# CH32V203_Wireless_Charge_V2_0.net
KiCad netlist of a schematic drawn in EasyEDA Pro
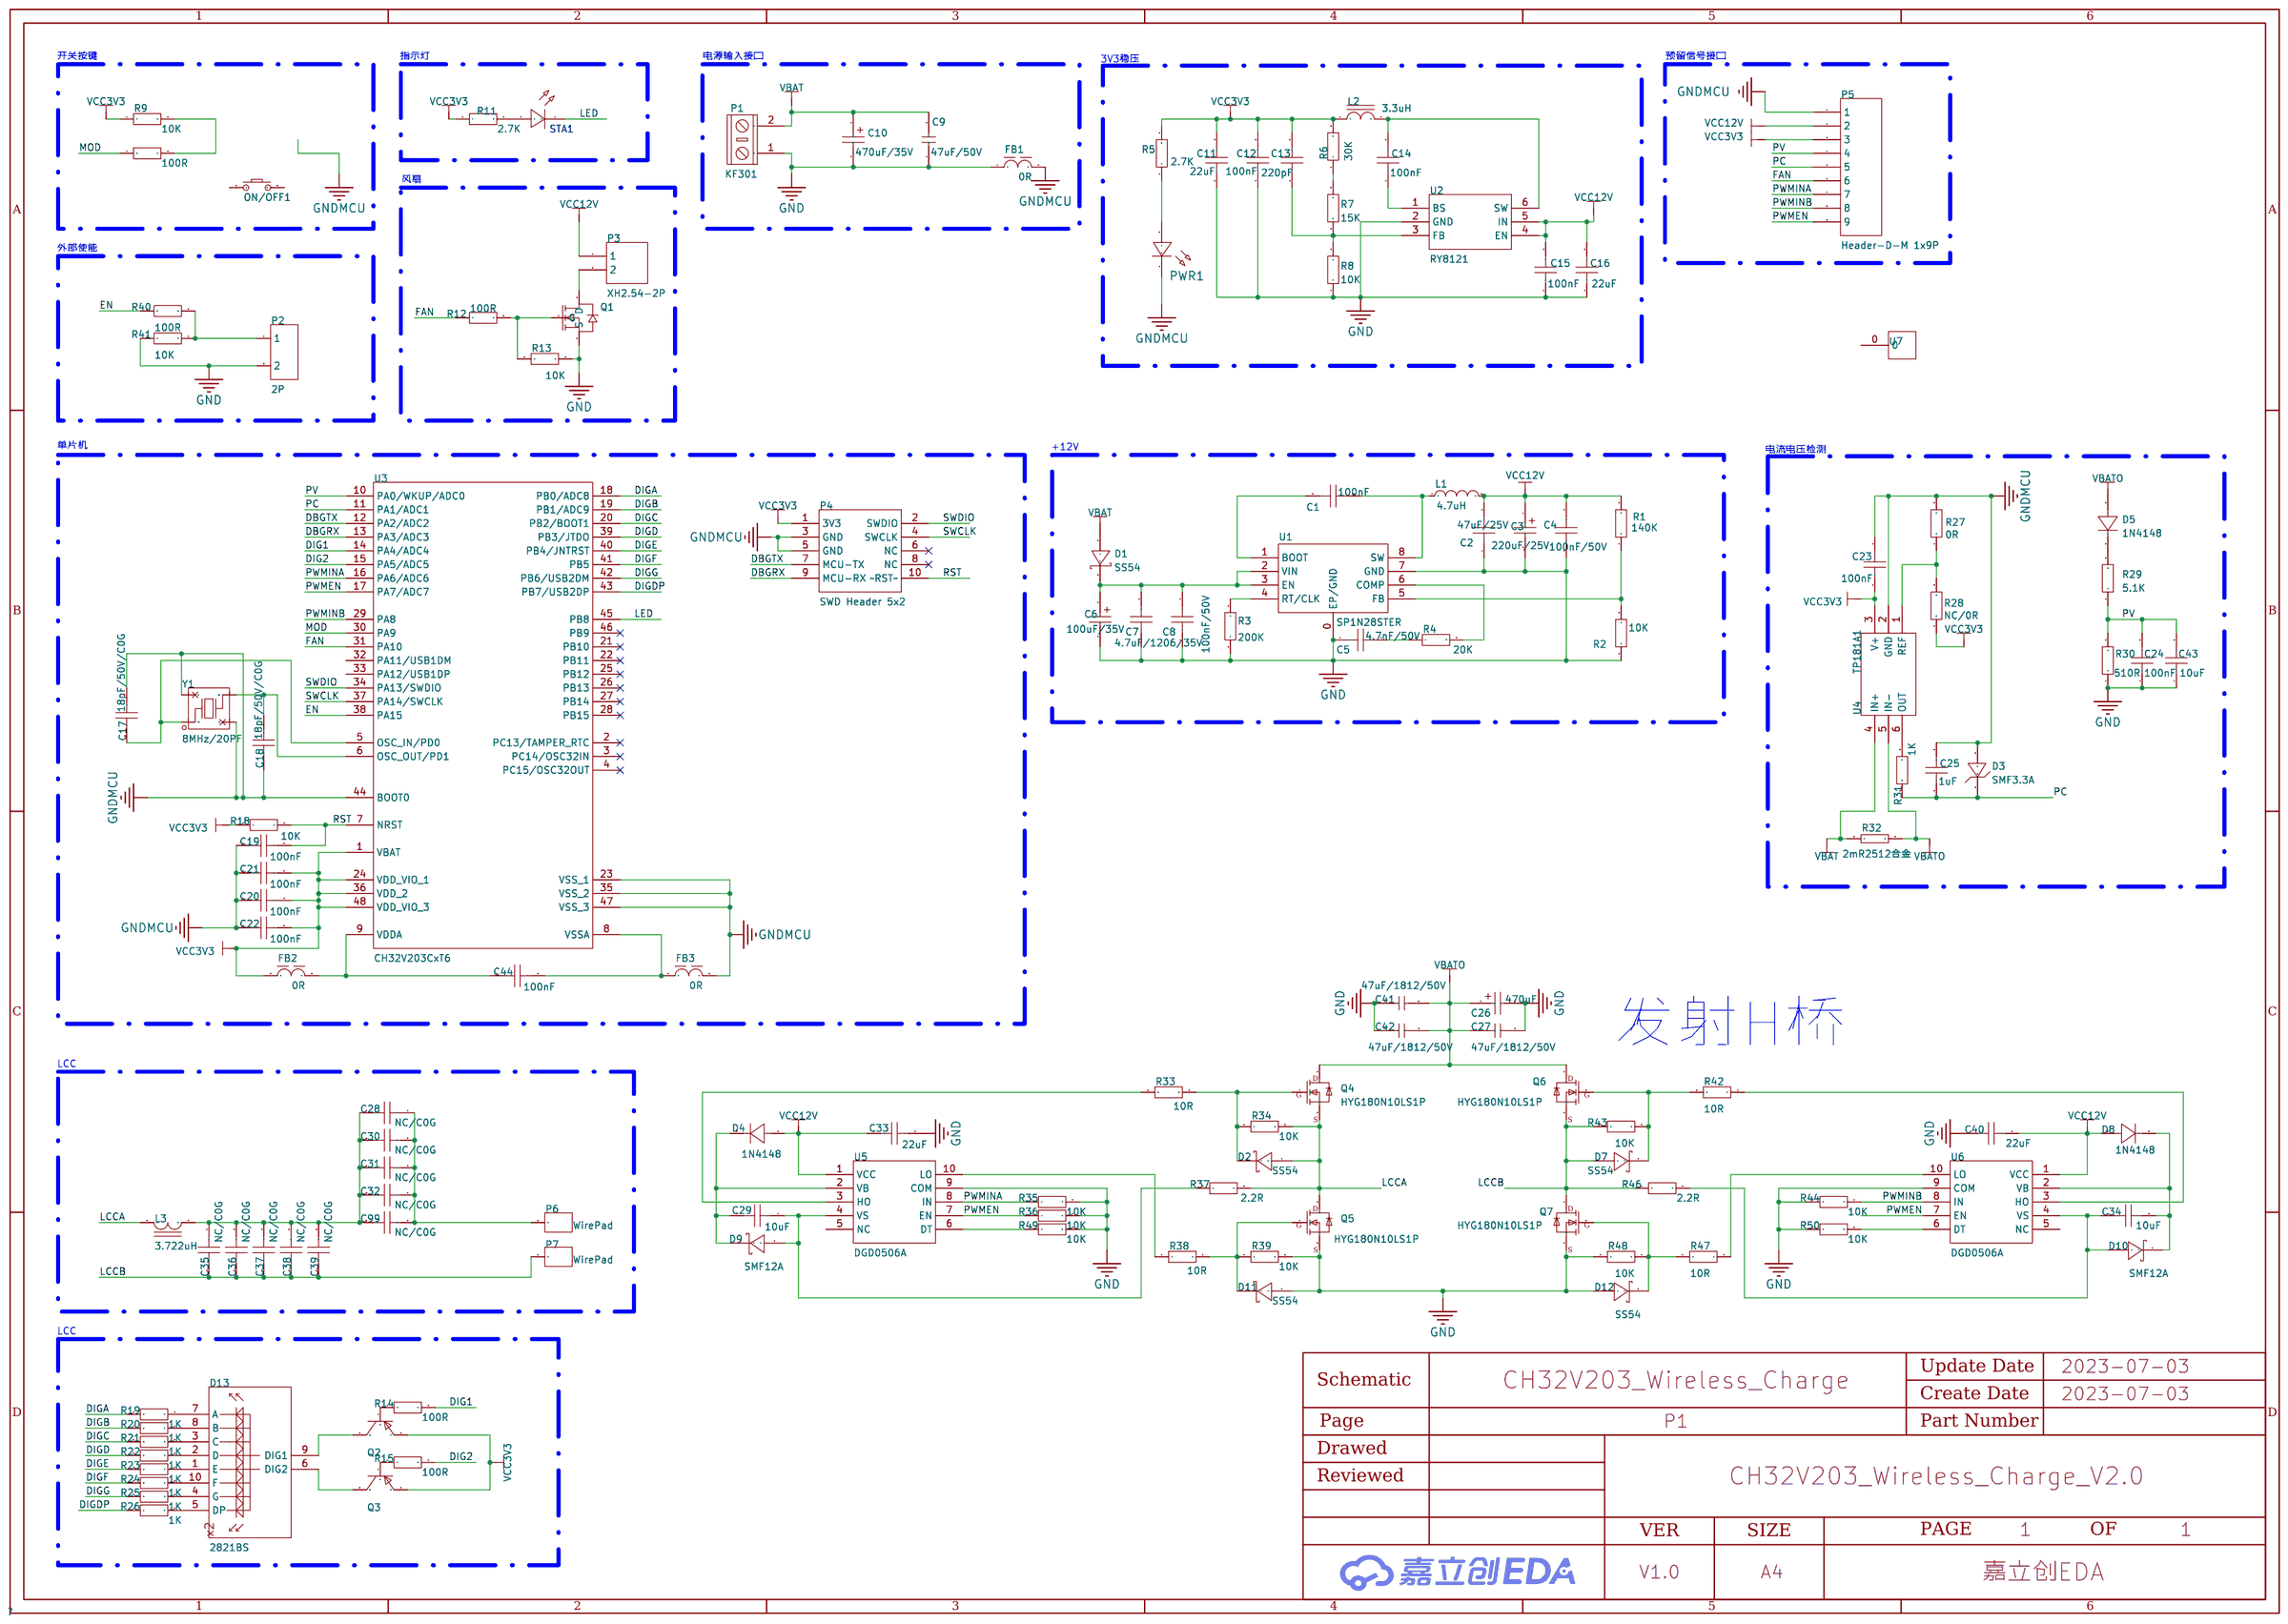
[diagram p0: schematic sheet]

(export (version "E")
  (design (tool "Eeschema 10.0.6"))
  (components
    (comp (ref "C1")
      (value "100nF")
      (footprint "easyedapro:C0603")
      (libsource (lib "easyedapro") (part "CapAcitance"))
    )
    (comp (ref "C2")
      (value "47uF/25V")
      (footprint "easyedapro:C0603")
      (libsource (lib "easyedapro") (part "CapAcitance"))
    )
    (comp (ref "C3")
      (value "220uF/25V")
      (footprint "easyedapro:Cap-S-D 2.5-6.3X8")
      (libsource (lib "easyedapro") (part "S-D 220uF 25V 6.3x8"))
    )
    (comp (ref "C4")
      (value "100nF/50V")
      (footprint "easyedapro:C0603")
      (libsource (lib "easyedapro") (part "CapAcitance"))
    )
    (comp (ref "C5")
      (value "4.7nF/50V")
      (footprint "easyedapro:C0603")
      (libsource (lib "easyedapro") (part "CapAcitance"))
    )
    (comp (ref "C6")
      (value "100uF/35V")
      (footprint "easyedapro:Cap-S-D 2.5-6.3X8")
      (libsource (lib "easyedapro") (part "S-D 100uF 35V 6.3x8"))
    )
    (comp (ref "C7")
      (value "4.7uF/1206/35V")
      (footprint "easyedapro:C0603")
      (libsource (lib "easyedapro") (part "CapAcitance"))
    )
    (comp (ref "C8")
      (value "100nF/50V")
      (footprint "easyedapro:C0603")
      (libsource (lib "easyedapro") (part "CapAcitance"))
    )
    (comp (ref "C9")
      (value "47uF/50V")
      (footprint "easyedapro:CAPC4532[1812]S")
      (libsource (lib "easyedapro") (part "47uF 1812 50V X5R"))
    )
    (comp (ref "C10")
      (value "470uF/35V")
      (footprint "easyedapro:Cap-S-D 3.5-8x14")
      (libsource (lib "easyedapro") (part "S-D 470uF 35V 8x14"))
    )
    (comp (ref "C11")
      (value "22uF")
      (footprint "easyedapro:C0603")
      (libsource (lib "easyedapro") (part "CapAcitance"))
    )
    (comp (ref "C12")
      (value "100nF")
      (footprint "easyedapro:C0603")
      (libsource (lib "easyedapro") (part "CapAcitance"))
    )
    (comp (ref "C13")
      (value "220pF")
      (footprint "easyedapro:C0603")
      (libsource (lib "easyedapro") (part "CapAcitance"))
    )
    (comp (ref "C14")
      (value "100nF")
      (footprint "easyedapro:C0603")
      (libsource (lib "easyedapro") (part "CapAcitance"))
    )
    (comp (ref "C15")
      (value "100nF")
      (footprint "easyedapro:C0603")
      (libsource (lib "easyedapro") (part "CapAcitance"))
    )
    (comp (ref "C16")
      (value "22uF")
      (footprint "easyedapro:C0603")
      (libsource (lib "easyedapro") (part "CapAcitance"))
    )
    (comp (ref "C17")
      (value "18pF/50V/C0G")
      (footprint "easyedapro:C0603")
      (libsource (lib "easyedapro") (part "CapAcitance"))
    )
    (comp (ref "C18")
      (value "18pF/50V/C0G")
      (footprint "easyedapro:C0603")
      (libsource (lib "easyedapro") (part "CapAcitance"))
    )
    (comp (ref "C19")
      (value "100nF")
      (footprint "easyedapro:C0603")
      (libsource (lib "easyedapro") (part "CapAcitance"))
    )
    (comp (ref "C20")
      (value "100nF")
      (footprint "easyedapro:C0603")
      (libsource (lib "easyedapro") (part "CapAcitance"))
    )
    (comp (ref "C21")
      (value "100nF")
      (footprint "easyedapro:C0603")
      (libsource (lib "easyedapro") (part "CapAcitance"))
    )
    (comp (ref "C22")
      (value "100nF")
      (footprint "easyedapro:C0603")
      (libsource (lib "easyedapro") (part "CapAcitance"))
    )
    (comp (ref "C23")
      (value "100nF")
      (footprint "easyedapro:C0603")
      (libsource (lib "easyedapro") (part "CapAcitance"))
    )
    (comp (ref "C24")
      (value "100nF")
      (footprint "easyedapro:C0603")
      (libsource (lib "easyedapro") (part "CapAcitance"))
    )
    (comp (ref "C25")
      (value "1uF")
      (footprint "easyedapro:C0603")
      (libsource (lib "easyedapro") (part "CapAcitance"))
    )
    (comp (ref "C26")
      (value "470uF")
      (footprint "easyedapro:Cap-S-D 3.5-8x14")
      (libsource (lib "easyedapro") (part "S-D 470uF 35V 8x14"))
    )
    (comp (ref "C27")
      (value "47uF/1812/50V")
      (footprint "easyedapro:CAPC4532[1812]S")
      (libsource (lib "easyedapro") (part "47uF 1812 50V X5R"))
    )
    (comp (ref "C28")
      (value "NC/C0G")
      (footprint "easyedapro:C0603")
      (libsource (lib "easyedapro") (part "CapAcitance"))
    )
    (comp (ref "C29")
      (value "10uF")
      (footprint "easyedapro:C0603")
      (libsource (lib "easyedapro") (part "CapAcitance"))
    )
    (comp (ref "C30")
      (value "NC/C0G")
      (footprint "easyedapro:C0603")
      (libsource (lib "easyedapro") (part "CapAcitance"))
    )
    (comp (ref "C31")
      (value "NC/C0G")
      (footprint "easyedapro:C0603")
      (libsource (lib "easyedapro") (part "CapAcitance"))
    )
    (comp (ref "C32")
      (value "NC/C0G")
      (footprint "easyedapro:C0603")
      (libsource (lib "easyedapro") (part "CapAcitance"))
    )
    (comp (ref "C33")
      (value "22uF")
      (footprint "easyedapro:C0603")
      (libsource (lib "easyedapro") (part "CapAcitance"))
    )
    (comp (ref "C34")
      (value "10uF")
      (footprint "easyedapro:C0603")
      (libsource (lib "easyedapro") (part "CapAcitance"))
    )
    (comp (ref "C35")
      (value "NC/C0G")
      (footprint "easyedapro:C0603")
      (libsource (lib "easyedapro") (part "CapAcitance"))
    )
    (comp (ref "C36")
      (value "NC/C0G")
      (footprint "easyedapro:C0603")
      (libsource (lib "easyedapro") (part "CapAcitance"))
    )
    (comp (ref "C37")
      (value "NC/C0G")
      (footprint "easyedapro:C0603")
      (libsource (lib "easyedapro") (part "CapAcitance"))
    )
    (comp (ref "C38")
      (value "NC/C0G")
      (footprint "easyedapro:C0603")
      (libsource (lib "easyedapro") (part "CapAcitance"))
    )
    (comp (ref "C39")
      (value "NC/C0G")
      (footprint "easyedapro:C0603")
      (libsource (lib "easyedapro") (part "CapAcitance"))
    )
    (comp (ref "C40")
      (value "22uF")
      (footprint "easyedapro:C0603")
      (libsource (lib "easyedapro") (part "CapAcitance"))
    )
    (comp (ref "C41")
      (value "47uF/1812/50V")
      (footprint "easyedapro:CAPC4532[1812]S")
      (libsource (lib "easyedapro") (part "47uF 1812 50V X5R"))
    )
    (comp (ref "C42")
      (value "47uF/1812/50V")
      (footprint "easyedapro:CAPC4532[1812]S")
      (libsource (lib "easyedapro") (part "47uF 1812 50V X5R"))
    )
    (comp (ref "C43")
      (value "10uF")
      (footprint "easyedapro:C0603")
      (libsource (lib "easyedapro") (part "CapAcitance"))
    )
    (comp (ref "C44")
      (value "100nF")
      (footprint "easyedapro:C0603")
      (libsource (lib "easyedapro") (part "CapAcitance"))
    )
    (comp (ref "C99")
      (value "NC/C0G")
      (footprint "easyedapro:C0603")
      (libsource (lib "easyedapro") (part "CapAcitance"))
    )
    (comp (ref "D1")
      (value "SS54")
      (footprint "easyedapro:SMA_L4.4-W2.8-LS5.4-R-RD")
      (description "直流反向耐压(Vr):40V;平均整流电流(Io):5A;正向压降(Vf):550mV@5A;")
      (fields (field (name "Manufacturer") "MDD"))
      (libsource (lib "easyedapro") (part "SS54_C22452"))
    )
    (comp (ref "D2")
      (value "SS54")
      (footprint "easyedapro:SMA_L4.4-W2.8-LS5.4-R-RD")
      (description "直流反向耐压(Vr):40V;平均整流电流(Io):5A;正向压降(Vf):550mV@5A;")
      (fields (field (name "Manufacturer") "MDD"))
      (libsource (lib "easyedapro") (part "SS54_C22452"))
    )
    (comp (ref "D3")
      (value "SMF3.3A")
      (footprint "easyedapro:SOD-123_L2.8-W1.8-LS3.7-RD")
      (description "极性:单向;反向截止电压(Vrwm):3.3V;击穿电压:5.2V;反向漏电流(Ir):600uA;峰值脉冲电流(Ipp)@10/1000μs:25A;最大钳位电压:8V;")
      (fields (field (name "Manufacturer") "DOWO(东沃)"))
      (libsource (lib "easyedapro") (part "SMF3.3A"))
    )
    (comp (ref "D4")
      (value "1N4148")
      (footprint "easyedapro:SOD-123_L2.7-W1.6-LS3.7-RD")
      (fields (field (name "Manufacturer") "FUXINSEMI(富芯森美)"))
      (libsource (lib "easyedapro") (part "1N4148W_C908248"))
    )
    (comp (ref "D5")
      (value "1N4148")
      (footprint "easyedapro:SOD-123_L2.7-W1.6-LS3.7-RD")
      (fields (field (name "Manufacturer") "FUXINSEMI(富芯森美)"))
      (libsource (lib "easyedapro") (part "1N4148W_C908248"))
    )
    (comp (ref "D7")
      (value "SS54")
      (footprint "easyedapro:SMA_L4.4-W2.8-LS5.4-R-RD")
      (description "直流反向耐压(Vr):40V;平均整流电流(Io):5A;正向压降(Vf):550mV@5A;")
      (fields (field (name "Manufacturer") "MDD"))
      (libsource (lib "easyedapro") (part "SS54_C22452"))
    )
    (comp (ref "D8")
      (value "1N4148")
      (footprint "easyedapro:SOD-123_L2.7-W1.6-LS3.7-RD")
      (fields (field (name "Manufacturer") "FUXINSEMI(富芯森美)"))
      (libsource (lib "easyedapro") (part "1N4148W_C908248"))
    )
    (comp (ref "D9")
      (value "SMF12A")
      (footprint "easyedapro:SOD-123F_L2.8-W1.8-LS3.7-RD")
      (description "极性:单向;反向截止电压(Vrwm):12V;击穿电压:13.3V;峰值脉冲电流(Ipp)@10/1000μs:-;最大钳位电压:19.9V;峰值脉冲功率(Ppp)@10/1000μs:200W;")
      (fields (field (name "Manufacturer") "Littelfuse(美国力特)"))
      (libsource (lib "easyedapro") (part "SMF12A_C207255"))
    )
    (comp (ref "D10")
      (value "SMF12A")
      (footprint "easyedapro:SOD-123F_L2.8-W1.8-LS3.7-RD")
      (description "极性:单向;反向截止电压(Vrwm):12V;击穿电压:13.3V;峰值脉冲电流(Ipp)@10/1000μs:-;最大钳位电压:19.9V;峰值脉冲功率(Ppp)@10/1000μs:200W;")
      (fields (field (name "Manufacturer") "Littelfuse(美国力特)"))
      (libsource (lib "easyedapro") (part "SMF12A_C207255"))
    )
    (comp (ref "D11")
      (value "SS54")
      (footprint "easyedapro:SMA_L4.4-W2.8-LS5.4-R-RD")
      (description "直流反向耐压(Vr):40V;平均整流电流(Io):5A;正向压降(Vf):550mV@5A;")
      (fields (field (name "Manufacturer") "MDD"))
      (libsource (lib "easyedapro") (part "SS54_C22452"))
    )
    (comp (ref "D12")
      (value "SS54")
      (footprint "easyedapro:SMA_L4.4-W2.8-LS5.4-R-RD")
      (description "直流反向耐压(Vr):40V;平均整流电流(Io):5A;正向压降(Vf):550mV@5A;")
      (fields (field (name "Manufacturer") "MDD"))
      (libsource (lib "easyedapro") (part "SS54_C22452"))
    )
    (comp (ref "D13")
      (value "2821BS")
      (footprint "easyedapro:2821AS/BS")
      (libsource (lib "easyedapro") (part "2821BS"))
    )
    (comp (ref "FB1")
      (value "0R")
      (footprint "easyedapro:INDC1608[0603]S")
      (libsource (lib "easyedapro") (part "FB-Chip"))
    )
    (comp (ref "FB2")
      (value "0R")
      (footprint "easyedapro:INDC1608[0603]S")
      (libsource (lib "easyedapro") (part "FB-Chip"))
    )
    (comp (ref "FB3")
      (value "0R")
      (footprint "easyedapro:INDC1608[0603]S")
      (libsource (lib "easyedapro") (part "FB-Chip"))
    )
    (comp (ref "L1")
      (value "4.7uH")
      (footprint "easyedapro:IND-SMD_L7.3-W6.6")
      (description "电感值:4.7uH;精度:±20%;额定电流:5.5A;饱和电流(Isat):7A;直流电阻(DCR):37mΩ;")
      (fields (field (name "Manufacturer Part") "MCS0630-4R7MPY1") (field (name "Manufacturer") "PSA(信昌电陶)"))
      (libsource (lib "easyedapro") (part "MCS0630-4R7MPY1"))
    )
    (comp (ref "L2")
      (value "3.3uH")
      (footprint "easyedapro:0402 TPC 4*4*2")
      (libsource (lib "easyedapro") (part "Ind-Power_1"))
    )
    (comp (ref "L3")
      (value "3.722uH")
      (footprint "easyedapro:T94/106-LAY")
      (libsource (lib "easyedapro") (part "Ind-Power_2"))
    )
    (comp (ref "ON/OFF1")
      (value "Button")
      (footprint "easyedapro:KEY-2-DIP-6*6-S")
      (libsource (lib "easyedapro") (part "KEY"))
    )
    (comp (ref "P1")
      (value "KF301")
      (footprint "easyedapro:KF/WJ/DG 301-2p-5.0mm")
      (libsource (lib "easyedapro") (part "KF/WJ/DG 30x"))
    )
    (comp (ref "P2")
      (value "2P")
      (footprint "easyedapro:HDR-TH_2P-P2.54-V-M-1")
      (fields (field (name "Manufacturer") "TEConnectivity(美国泰科)"))
      (libsource (lib "easyedapro") (part "Header-Male-2.54_1x2"))
    )
    (comp (ref "P3")
      (value "XH2.54-2P")
      (footprint "easyedapro:XH2.54-2P-DV")
      (libsource (lib "easyedapro") (part "XH2.54-2P"))
    )
    (comp (ref "P4")
      (value "SWD Header 5x2")
      (footprint "easyedapro:HDR2X5-M")
      (libsource (lib "easyedapro") (part "SWD Header 5x2"))
    )
    (comp (ref "P5")
      (value "Header-D-M1x9P")
      (footprint "easyedapro:HDR1X9-M")
      (libsource (lib "easyedapro") (part "Header-D-M 1x9P"))
    )
    (comp (ref "P6")
      (value "WirePad")
      (footprint "easyedapro:WirePad-4x6")
      (libsource (lib "easyedapro") (part "WirePad"))
    )
    (comp (ref "P7")
      (value "WirePad")
      (footprint "easyedapro:WirePad-4x6")
      (libsource (lib "easyedapro") (part "WirePad"))
    )
    (comp (ref "PWR1")
      (value "~")
      (footprint "easyedapro:LED_0603")
      (libsource (lib "easyedapro") (part "LED_R"))
    )
    (comp (ref "Q1")
      (value "~")
      (footprint "easyedapro:SOT-23-3_L2.9-W1.3-P1.90-LS2.4-BR")
      (libsource (lib "easyedapro") (part "N_MOS"))
    )
    (comp (ref "Q2")
      (value "~")
      (footprint "easyedapro:S8550P_SOT")
      (libsource (lib "easyedapro") (part "PNP"))
    )
    (comp (ref "Q3")
      (value "~")
      (footprint "easyedapro:S8550P_SOT")
      (libsource (lib "easyedapro") (part "PNP"))
    )
    (comp (ref "Q4")
      (value "HYG180N10LS1P")
      (footprint "easyedapro:TO-220-LAY")
      (libsource (lib "easyedapro") (part "HYG180N10LS1P"))
    )
    (comp (ref "Q5")
      (value "HYG180N10LS1P")
      (footprint "easyedapro:TO-220-LAY")
      (libsource (lib "easyedapro") (part "HYG180N10LS1P"))
    )
    (comp (ref "Q6")
      (value "HYG180N10LS1P")
      (footprint "easyedapro:TO-220-LAY")
      (libsource (lib "easyedapro") (part "HYG180N10LS1P"))
    )
    (comp (ref "Q7")
      (value "HYG180N10LS1P")
      (footprint "easyedapro:TO-220-LAY")
      (libsource (lib "easyedapro") (part "HYG180N10LS1P"))
    )
    (comp (ref "R1") (value "140K") (footprint "easyedapro:R0603") (libsource (lib "easyedapro") (part "电阻")))
    (comp (ref "R2") (value "10K") (footprint "easyedapro:R0603") (libsource (lib "easyedapro") (part "电阻")))
    (comp (ref "R3") (value "200K") (footprint "easyedapro:R0603") (libsource (lib "easyedapro") (part "电阻")))
    (comp (ref "R4") (value "20K") (footprint "easyedapro:R0603") (libsource (lib "easyedapro") (part "电阻")))
    (comp (ref "R5") (value "2.7K") (footprint "easyedapro:R0603") (libsource (lib "easyedapro") (part "电阻")))
    (comp (ref "R6") (value "30K") (footprint "easyedapro:R0603") (libsource (lib "easyedapro") (part "电阻")))
    (comp (ref "R7") (value "15K") (footprint "easyedapro:R0603") (libsource (lib "easyedapro") (part "电阻")))
    (comp (ref "R8") (value "10K") (footprint "easyedapro:R0603") (libsource (lib "easyedapro") (part "电阻")))
    (comp (ref "R9") (value "10K") (footprint "easyedapro:R0603") (libsource (lib "easyedapro") (part "电阻")))
    (comp (ref "R10")
      (value "100R")
      (footprint "easyedapro:R0603")
      (libsource (lib "easyedapro") (part "电阻"))
    )
    (comp (ref "R11")
      (value "2.7K")
      (footprint "easyedapro:R0603")
      (libsource (lib "easyedapro") (part "电阻"))
    )
    (comp (ref "R12")
      (value "100R")
      (footprint "easyedapro:R0603")
      (libsource (lib "easyedapro") (part "电阻"))
    )
    (comp (ref "R13") (value "10K") (footprint "easyedapro:R0603") (libsource (lib "easyedapro") (part "电阻")))
    (comp (ref "R14")
      (value "100R")
      (footprint "easyedapro:R0603")
      (libsource (lib "easyedapro") (part "电阻"))
    )
    (comp (ref "R15")
      (value "100R")
      (footprint "easyedapro:R0603")
      (libsource (lib "easyedapro") (part "电阻"))
    )
    (comp (ref "R18") (value "10K") (footprint "easyedapro:R0603") (libsource (lib "easyedapro") (part "电阻")))
    (comp (ref "R19") (value "1K") (footprint "easyedapro:R0603") (libsource (lib "easyedapro") (part "电阻")))
    (comp (ref "R20") (value "1K") (footprint "easyedapro:R0603") (libsource (lib "easyedapro") (part "电阻")))
    (comp (ref "R21") (value "1K") (footprint "easyedapro:R0603") (libsource (lib "easyedapro") (part "电阻")))
    (comp (ref "R22") (value "1K") (footprint "easyedapro:R0603") (libsource (lib "easyedapro") (part "电阻")))
    (comp (ref "R23") (value "1K") (footprint "easyedapro:R0603") (libsource (lib "easyedapro") (part "电阻")))
    (comp (ref "R24") (value "1K") (footprint "easyedapro:R0603") (libsource (lib "easyedapro") (part "电阻")))
    (comp (ref "R25") (value "1K") (footprint "easyedapro:R0603") (libsource (lib "easyedapro") (part "电阻")))
    (comp (ref "R26") (value "1K") (footprint "easyedapro:R0603") (libsource (lib "easyedapro") (part "电阻")))
    (comp (ref "R27") (value "0R") (footprint "easyedapro:R0603") (libsource (lib "easyedapro") (part "电阻")))
    (comp (ref "R28")
      (value "NC/0R")
      (footprint "easyedapro:R0603")
      (libsource (lib "easyedapro") (part "电阻"))
    )
    (comp (ref "R29")
      (value "5.1K")
      (footprint "easyedapro:R0603")
      (libsource (lib "easyedapro") (part "电阻"))
    )
    (comp (ref "R30")
      (value "510R")
      (footprint "easyedapro:R0603")
      (libsource (lib "easyedapro") (part "电阻"))
    )
    (comp (ref "R31") (value "1K") (footprint "easyedapro:R0603") (libsource (lib "easyedapro") (part "电阻")))
    (comp (ref "R32")
      (value "2mR2512合金")
      (footprint "easyedapro:RESC6332[2512]S")
      (libsource (lib "easyedapro") (part "Res-Chip_10"))
    )
    (comp (ref "R33") (value "10R") (footprint "easyedapro:R0603") (libsource (lib "easyedapro") (part "电阻")))
    (comp (ref "R34") (value "10K") (footprint "easyedapro:R0603") (libsource (lib "easyedapro") (part "电阻")))
    (comp (ref "R35") (value "10K") (footprint "easyedapro:R0603") (libsource (lib "easyedapro") (part "电阻")))
    (comp (ref "R36") (value "10K") (footprint "easyedapro:R0603") (libsource (lib "easyedapro") (part "电阻")))
    (comp (ref "R37")
      (value "2.2R")
      (footprint "easyedapro:R0603")
      (libsource (lib "easyedapro") (part "电阻"))
    )
    (comp (ref "R38") (value "10R") (footprint "easyedapro:R0603") (libsource (lib "easyedapro") (part "电阻")))
    (comp (ref "R39") (value "10K") (footprint "easyedapro:R0603") (libsource (lib "easyedapro") (part "电阻")))
    (comp (ref "R40")
      (value "100R")
      (footprint "easyedapro:R0603")
      (libsource (lib "easyedapro") (part "电阻"))
    )
    (comp (ref "R41") (value "10K") (footprint "easyedapro:R0603") (libsource (lib "easyedapro") (part "电阻")))
    (comp (ref "R42") (value "10R") (footprint "easyedapro:R0603") (libsource (lib "easyedapro") (part "电阻")))
    (comp (ref "R43") (value "10K") (footprint "easyedapro:R0603") (libsource (lib "easyedapro") (part "电阻")))
    (comp (ref "R44") (value "10K") (footprint "easyedapro:R0603") (libsource (lib "easyedapro") (part "电阻")))
    (comp (ref "R46")
      (value "2.2R")
      (footprint "easyedapro:R0603")
      (libsource (lib "easyedapro") (part "电阻"))
    )
    (comp (ref "R47") (value "10R") (footprint "easyedapro:R0603") (libsource (lib "easyedapro") (part "电阻")))
    (comp (ref "R48") (value "10K") (footprint "easyedapro:R0603") (libsource (lib "easyedapro") (part "电阻")))
    (comp (ref "R49") (value "10K") (footprint "easyedapro:R0603") (libsource (lib "easyedapro") (part "电阻")))
    (comp (ref "R50") (value "10K") (footprint "easyedapro:R0603") (libsource (lib "easyedapro") (part "电阻")))
    (comp (ref "STA1")
      (value "~")
      (footprint "easyedapro:LED_0603")
      (libsource (lib "easyedapro") (part "LED_B"))
    )
    (comp (ref "U1") (value "SP1N28STER") (libsource (lib "easyedapro") (part "SP1N28STER")))
    (comp (ref "U2")
      (value "RY8121")
      (footprint "easyedapro:SOT-23-6")
      (libsource (lib "easyedapro") (part "RY8121"))
    )
    (comp (ref "U3")
      (value "CH32V203CxT6")
      (footprint "easyedapro:LQFP48_L")
      (libsource (lib "easyedapro") (part "CH32V203CxT6"))
    )
    (comp (ref "U4")
      (value "TP181A1")
      (footprint "easyedapro:SOT-363")
      (libsource (lib "easyedapro") (part "TP181Ax"))
    )
    (comp (ref "U5")
      (value "DGD0506A")
      (footprint "easyedapro:MSOP-10")
      (libsource (lib "easyedapro") (part "DGD0506A"))
    )
    (comp (ref "U6")
      (value "DGD0506A")
      (footprint "easyedapro:MSOP-10")
      (libsource (lib "easyedapro") (part "DGD0506A"))
    )
    (comp (ref "U7") (value "~") (libsource (lib "easyedapro") (part "fan")))
    (comp (ref "Y1")
      (value "8MHz/20PF")
      (footprint "easyedapro:X3225-4")
      (libsource (lib "easyedapro") (part "XTAL-4"))
    )
  )
  (nets
    (net (code "1") (name "/DBGRX") (class "Default")
      (node (ref "P4") (pin "9") (pinfunction "MCU-RX_9") (pintype "input"))
      (node (ref "U3") (pin "13") (pinfunction "PA3/ADC3_13") (pintype "input"))
    )
    (net (code "2") (name "/DBGTX") (class "Default")
      (node (ref "P4") (pin "7") (pinfunction "MCU-TX_7") (pintype "input"))
      (node (ref "U3") (pin "12") (pinfunction "PA2/ADC2_12") (pintype "input"))
    )
    (net (code "3") (name "/DIG1") (class "Default")
      (node (ref "R14") (pin "2") (pinfunction "2_2") (pintype "input"))
      (node (ref "U3") (pin "14") (pinfunction "PA4/ADC4_14") (pintype "input"))
    )
    (net (code "4") (name "/DIG2") (class "Default")
      (node (ref "R15") (pin "2") (pinfunction "2_2") (pintype "input"))
      (node (ref "U3") (pin "15") (pinfunction "PA5/ADC5_15") (pintype "input"))
    )
    (net (code "5") (name "/DIGA") (class "Default")
      (node (ref "R19") (pin "1") (pinfunction "1_1") (pintype "input"))
      (node (ref "U3") (pin "18") (pinfunction "PB0/ADC8_18") (pintype "input"))
    )
    (net (code "6") (name "/DIGB") (class "Default")
      (node (ref "R20") (pin "1") (pinfunction "1_1") (pintype "input"))
      (node (ref "U3") (pin "19") (pinfunction "PB1/ADC9_19") (pintype "input"))
    )
    (net (code "7") (name "/DIGC") (class "Default")
      (node (ref "R21") (pin "1") (pinfunction "1_1") (pintype "input"))
      (node (ref "U3") (pin "20") (pinfunction "PB2/BOOT1_20") (pintype "input"))
    )
    (net (code "8") (name "/DIGD") (class "Default")
      (node (ref "R22") (pin "1") (pinfunction "1_1") (pintype "input"))
      (node (ref "U3") (pin "39") (pinfunction "PB3/JTDO_39") (pintype "input"))
    )
    (net (code "9") (name "/DIGDP") (class "Default")
      (node (ref "R26") (pin "1") (pinfunction "1_1") (pintype "input"))
      (node (ref "U3") (pin "43") (pinfunction "PB7/USB2DP_43") (pintype "input"))
    )
    (net (code "10") (name "/DIGE") (class "Default")
      (node (ref "R23") (pin "1") (pinfunction "1_1") (pintype "input"))
      (node (ref "U3") (pin "40") (pinfunction "PB4/JNTRST_40") (pintype "input"))
    )
    (net (code "11") (name "/DIGF") (class "Default")
      (node (ref "R24") (pin "1") (pinfunction "1_1") (pintype "input"))
      (node (ref "U3") (pin "41") (pinfunction "PB5_41") (pintype "input"))
    )
    (net (code "12") (name "/DIGG") (class "Default")
      (node (ref "R25") (pin "1") (pinfunction "1_1") (pintype "input"))
      (node (ref "U3") (pin "42") (pinfunction "PB6/USB2DM_42") (pintype "input"))
    )
    (net (code "13") (name "/EN") (class "Default")
      (node (ref "R40") (pin "1") (pinfunction "1_1") (pintype "input"))
      (node (ref "U3") (pin "38") (pinfunction "PA15_38") (pintype "input"))
    )
    (net (code "14") (name "/FAN") (class "Default")
      (node (ref "P5") (pin "6") (pinfunction "6_6") (pintype "input"))
      (node (ref "R12") (pin "1") (pinfunction "1_1") (pintype "input"))
      (node (ref "U3") (pin "31") (pinfunction "PA10_31") (pintype "input"))
    )
    (net (code "15") (name "/LCCA") (class "Default")
      (node (ref "D2") (pin "1") (pinfunction "A_1") (pintype "input"))
      (node (ref "L3") (pin "2") (pinfunction "2_2") (pintype "input"))
      (node (ref "Q4") (pin "3") (pinfunction "S_3") (pintype "input"))
      (node (ref "Q5") (pin "2") (pinfunction "D_2") (pintype "input"))
      (node (ref "R34") (pin "2") (pinfunction "2_2") (pintype "input"))
      (node (ref "R37") (pin "2") (pinfunction "2_2") (pintype "input"))
    )
    (net (code "16") (name "/LCCB") (class "Default")
      (node (ref "C35") (pin "1") (pinfunction "1_1") (pintype "input"))
      (node (ref "C36") (pin "1") (pinfunction "1_1") (pintype "input"))
      (node (ref "C37") (pin "1") (pinfunction "1_1") (pintype "input"))
      (node (ref "C38") (pin "1") (pinfunction "1_1") (pintype "input"))
      (node (ref "C39") (pin "1") (pinfunction "1_1") (pintype "input"))
      (node (ref "D7") (pin "1") (pinfunction "A_1") (pintype "input"))
      (node (ref "P7") (pin "1") (pinfunction "1_1") (pintype "input"))
      (node (ref "Q6") (pin "3") (pinfunction "S_3") (pintype "input"))
      (node (ref "Q7") (pin "2") (pinfunction "D_2") (pintype "input"))
      (node (ref "R43") (pin "2") (pinfunction "2_2") (pintype "input"))
      (node (ref "R46") (pin "2") (pinfunction "2_2") (pintype "input"))
    )
    (net (code "17") (name "/LED") (class "Default")
      (node (ref "STA1") (pin "1") (pinfunction "C_1") (pintype "input"))
      (node (ref "U3") (pin "45") (pinfunction "PB8_45") (pintype "input"))
    )
    (net (code "18") (name "/MOD") (class "Default")
      (node (ref "R10") (pin "1") (pinfunction "1_1") (pintype "input"))
      (node (ref "U3") (pin "30") (pinfunction "PA9_30") (pintype "input"))
    )
    (net (code "19") (name "/PC") (class "Default")
      (node (ref "C25") (pin "1") (pinfunction "1_1") (pintype "input"))
      (node (ref "D3") (pin "1") (pinfunction "1_1") (pintype "input"))
      (node (ref "P5") (pin "5") (pinfunction "5_5") (pintype "input"))
      (node (ref "R31") (pin "1") (pinfunction "1_1") (pintype "input"))
      (node (ref "U3") (pin "11") (pinfunction "PA1/ADC1_11") (pintype "input"))
    )
    (net (code "20") (name "/PV") (class "Default")
      (node (ref "C24") (pin "2") (pinfunction "2_2") (pintype "input"))
      (node (ref "C43") (pin "2") (pinfunction "2_2") (pintype "input"))
      (node (ref "P5") (pin "4") (pinfunction "4_4") (pintype "input"))
      (node (ref "R29") (pin "1") (pinfunction "1_1") (pintype "input"))
      (node (ref "R30") (pin "2") (pinfunction "2_2") (pintype "input"))
      (node (ref "U3") (pin "10") (pinfunction "PA0/WKUP/ADC0_10") (pintype "input"))
    )
    (net (code "21") (name "/PWMEN") (class "Default")
      (node (ref "P5") (pin "9") (pinfunction "9_9") (pintype "input"))
      (node (ref "R36") (pin "1") (pinfunction "1_1") (pintype "input"))
      (node (ref "U3") (pin "17") (pinfunction "PA7/ADC7_17") (pintype "input"))
      (node (ref "U5") (pin "7") (pinfunction "EN_7") (pintype "input"))
      (node (ref "U6") (pin "7") (pinfunction "EN_7") (pintype "input"))
    )
    (net (code "22") (name "/PWMINA") (class "Default")
      (node (ref "P5") (pin "7") (pinfunction "7_7") (pintype "input"))
      (node (ref "R35") (pin "1") (pinfunction "1_1") (pintype "input"))
      (node (ref "U3") (pin "16") (pinfunction "PA6/ADC6_16") (pintype "input"))
      (node (ref "U5") (pin "8") (pinfunction "IN_8") (pintype "input"))
    )
    (net (code "23") (name "/PWMINB") (class "Default")
      (node (ref "P5") (pin "8") (pinfunction "8_8") (pintype "input"))
      (node (ref "R44") (pin "1") (pinfunction "1_1") (pintype "input"))
      (node (ref "U3") (pin "29") (pinfunction "PA8_29") (pintype "input"))
      (node (ref "U6") (pin "8") (pinfunction "IN_8") (pintype "input"))
    )
    (net (code "24") (name "/RST") (class "Default")
      (node (ref "C19") (pin "2") (pinfunction "2_2") (pintype "input"))
      (node (ref "P4") (pin "10") (pinfunction "~RST~_10") (pintype "input"))
      (node (ref "R18") (pin "2") (pinfunction "2_2") (pintype "input"))
      (node (ref "U3") (pin "7") (pinfunction "NRST_7") (pintype "input"))
    )
    (net (code "25") (name "/SWCLK") (class "Default")
      (node (ref "P4") (pin "4") (pinfunction "SWCLK_4") (pintype "input"))
      (node (ref "U3") (pin "37") (pinfunction "PA14/SWCLK_37") (pintype "input"))
    )
    (net (code "26") (name "/SWDIO") (class "Default")
      (node (ref "P4") (pin "2") (pinfunction "SWDIO_2") (pintype "input"))
      (node (ref "U3") (pin "34") (pinfunction "PA13/SWDIO_34") (pintype "input"))
    )
    (net (code "27") (name "GND") (class "Default")
      (node (ref "C10") (pin "2") (pinfunction "2_2") (pintype "input"))
      (node (ref "C11") (pin "1") (pinfunction "1_1") (pintype "input"))
      (node (ref "C12") (pin "1") (pinfunction "1_1") (pintype "input"))
      (node (ref "C15") (pin "1") (pinfunction "1_1") (pintype "input"))
      (node (ref "C16") (pin "1") (pinfunction "1_1") (pintype "input"))
      (node (ref "C2") (pin "1") (pinfunction "1_1") (pintype "input"))
      (node (ref "C24") (pin "1") (pinfunction "1_1") (pintype "input"))
      (node (ref "C26") (pin "2") (pinfunction "2_2") (pintype "input"))
      (node (ref "C27") (pin "2") (pinfunction "2_2") (pintype "input"))
      (node (ref "C3") (pin "2") (pinfunction "2_2") (pintype "input"))
      (node (ref "C33") (pin "1") (pinfunction "1_1") (pintype "input"))
      (node (ref "C4") (pin "1") (pinfunction "1_1") (pintype "input"))
      (node (ref "C40") (pin "1") (pinfunction "1_1") (pintype "input"))
      (node (ref "C41") (pin "1") (pinfunction "1_1") (pintype "input"))
      (node (ref "C42") (pin "1") (pinfunction "1_1") (pintype "input"))
      (node (ref "C43") (pin "1") (pinfunction "1_1") (pintype "input"))
      (node (ref "C5") (pin "1") (pinfunction "1_1") (pintype "input"))
      (node (ref "C6") (pin "2") (pinfunction "2_2") (pintype "input"))
      (node (ref "C7") (pin "1") (pinfunction "1_1") (pintype "input"))
      (node (ref "C8") (pin "1") (pinfunction "1_1") (pintype "input"))
      (node (ref "C9") (pin "1") (pinfunction "1_1") (pintype "input"))
      (node (ref "D11") (pin "1") (pinfunction "A_1") (pintype "input"))
      (node (ref "D12") (pin "1") (pinfunction "A_1") (pintype "input"))
      (node (ref "FB1") (pin "1") (pinfunction "1_1") (pintype "input"))
      (node (ref "P1") (pin "1") (pinfunction "1_1") (pintype "input"))
      (node (ref "P2") (pin "2") (pinfunction "2_2") (pintype "input"))
      (node (ref "Q1") (pin "2") (pinfunction "S_2") (pintype "input"))
      (node (ref "Q5") (pin "3") (pinfunction "S_3") (pintype "input"))
      (node (ref "Q7") (pin "3") (pinfunction "S_3") (pintype "input"))
      (node (ref "R13") (pin "2") (pinfunction "2_2") (pintype "input"))
      (node (ref "R2") (pin "1") (pinfunction "1_1") (pintype "input"))
      (node (ref "R3") (pin "1") (pinfunction "1_1") (pintype "input"))
      (node (ref "R30") (pin "1") (pinfunction "1_1") (pintype "input"))
      (node (ref "R35") (pin "2") (pinfunction "2_2") (pintype "input"))
      (node (ref "R36") (pin "2") (pinfunction "2_2") (pintype "input"))
      (node (ref "R39") (pin "2") (pinfunction "2_2") (pintype "input"))
      (node (ref "R41") (pin "1") (pinfunction "1_1") (pintype "input"))
      (node (ref "R44") (pin "2") (pinfunction "2_2") (pintype "input"))
      (node (ref "R48") (pin "2") (pinfunction "2_2") (pintype "input"))
      (node (ref "R49") (pin "2") (pinfunction "2_2") (pintype "input"))
      (node (ref "R50") (pin "2") (pinfunction "2_2") (pintype "input"))
      (node (ref "R8") (pin "1") (pinfunction "1_1") (pintype "input"))
      (node (ref "U1") (pin "0") (pinfunction "EP/GND_0") (pintype "input"))
      (node (ref "U1") (pin "7") (pinfunction "GND_7") (pintype "input"))
      (node (ref "U2") (pin "2") (pinfunction "GND_2") (pintype "input"))
      (node (ref "U5") (pin "9") (pinfunction "COM_9") (pintype "input"))
      (node (ref "U6") (pin "9") (pinfunction "COM_9") (pintype "input"))
    )
    (net (code "28") (name "GNDMCU") (class "Default")
      (node (ref "C17") (pin "2") (pinfunction "2_2") (pintype "input"))
      (node (ref "C18") (pin "1") (pinfunction "1_1") (pintype "input"))
      (node (ref "C19") (pin "1") (pinfunction "1_1") (pintype "input"))
      (node (ref "C20") (pin "1") (pinfunction "1_1") (pintype "input"))
      (node (ref "C21") (pin "1") (pinfunction "1_1") (pintype "input"))
      (node (ref "C22") (pin "1") (pinfunction "1_1") (pintype "input"))
      (node (ref "C23") (pin "2") (pinfunction "2_2") (pintype "input"))
      (node (ref "C25") (pin "2") (pinfunction "2_2") (pintype "input"))
      (node (ref "D3") (pin "2") (pinfunction "2_2") (pintype "input"))
      (node (ref "FB1") (pin "2") (pinfunction "2_2") (pintype "input"))
      (node (ref "FB3") (pin "2") (pinfunction "2_2") (pintype "input"))
      (node (ref "P4") (pin "3") (pinfunction "GND_3") (pintype "input"))
      (node (ref "P4") (pin "5") (pinfunction "GND_5") (pintype "input"))
      (node (ref "P5") (pin "1") (pinfunction "1_1") (pintype "input"))
      (node (ref "PWR1") (pin "1") (pinfunction "C_1") (pintype "input"))
      (node (ref "R27") (pin "2") (pinfunction "2_2") (pintype "input"))
      (node (ref "U3") (pin "23") (pinfunction "VSS_1_23") (pintype "input"))
      (node (ref "U3") (pin "35") (pinfunction "VSS_2_35") (pintype "input"))
      (node (ref "U3") (pin "44") (pinfunction "BOOT0_44") (pintype "input"))
      (node (ref "U3") (pin "47") (pinfunction "VSS_3_47") (pintype "input"))
      (node (ref "U4") (pin "2") (pinfunction "GND_2") (pintype "input"))
      (node (ref "Y1") (pin "2") (pinfunction "NC_2") (pintype "input"))
      (node (ref "Y1") (pin "4") (pinfunction "NC_4") (pintype "input"))
    )
    (net (code "29") (name "Net-(C5-Pad2)") (class "Default")
      (node (ref "C5") (pin "2") (pinfunction "2_2") (pintype "input"))
      (node (ref "R4") (pin "1") (pinfunction "1_1") (pintype "input"))
    )
    (net (code "30") (name "Net-(C28-Pad1)") (class "Default")
      (node (ref "C28") (pin "1") (pinfunction "1_1") (pintype "input"))
      (node (ref "C30") (pin "1") (pinfunction "1_1") (pintype "input"))
      (node (ref "C31") (pin "1") (pinfunction "1_1") (pintype "input"))
      (node (ref "C32") (pin "1") (pinfunction "1_1") (pintype "input"))
      (node (ref "C99") (pin "1") (pinfunction "1_1") (pintype "input"))
      (node (ref "P6") (pin "1") (pinfunction "1_1") (pintype "input"))
    )
    (net (code "31") (name "Net-(C28-Pad2)") (class "Default")
      (node (ref "C28") (pin "2") (pinfunction "2_2") (pintype "input"))
      (node (ref "C30") (pin "2") (pinfunction "2_2") (pintype "input"))
      (node (ref "C31") (pin "2") (pinfunction "2_2") (pintype "input"))
      (node (ref "C32") (pin "2") (pinfunction "2_2") (pintype "input"))
      (node (ref "C35") (pin "2") (pinfunction "2_2") (pintype "input"))
      (node (ref "C36") (pin "2") (pinfunction "2_2") (pintype "input"))
      (node (ref "C37") (pin "2") (pinfunction "2_2") (pintype "input"))
      (node (ref "C38") (pin "2") (pinfunction "2_2") (pintype "input"))
      (node (ref "C39") (pin "2") (pinfunction "2_2") (pintype "input"))
      (node (ref "C99") (pin "2") (pinfunction "2_2") (pintype "input"))
      (node (ref "L3") (pin "1") (pinfunction "1_1") (pintype "input"))
    )
    (net (code "32") (name "Net-(D1-K)") (class "Default")
      (node (ref "C6") (pin "1") (pinfunction "1_1") (pintype "input"))
      (node (ref "C7") (pin "2") (pinfunction "2_2") (pintype "input"))
      (node (ref "C8") (pin "2") (pinfunction "2_2") (pintype "input"))
      (node (ref "D1") (pin "2") (pinfunction "K_2") (pintype "input"))
      (node (ref "U1") (pin "2") (pinfunction "VIN_2") (pintype "input"))
      (node (ref "U1") (pin "3") (pinfunction "EN_3") (pintype "input"))
    )
    (net (code "33") (name "Net-(D2-K)") (class "Default")
      (node (ref "D2") (pin "2") (pinfunction "K_2") (pintype "input"))
      (node (ref "Q4") (pin "1") (pinfunction "G_1") (pintype "input"))
      (node (ref "R33") (pin "2") (pinfunction "2_2") (pintype "input"))
      (node (ref "R34") (pin "1") (pinfunction "1_1") (pintype "input"))
    )
    (net (code "34") (name "Net-(D4-K)") (class "Default")
      (node (ref "C29") (pin "2") (pinfunction "2_2") (pintype "input"))
      (node (ref "D4") (pin "1") (pinfunction "K_1") (pintype "input"))
      (node (ref "D9") (pin "1") (pinfunction "K_1") (pintype "input"))
      (node (ref "U5") (pin "2") (pinfunction "VB_2") (pintype "input"))
    )
    (net (code "35") (name "Net-(D5-K)") (class "Default")
      (node (ref "D5") (pin "1") (pinfunction "K_1") (pintype "input"))
      (node (ref "R29") (pin "2") (pinfunction "2_2") (pintype "input"))
    )
    (net (code "36") (name "Net-(D7-K)") (class "Default")
      (node (ref "D7") (pin "2") (pinfunction "K_2") (pintype "input"))
      (node (ref "Q6") (pin "1") (pinfunction "G_1") (pintype "input"))
      (node (ref "R42") (pin "2") (pinfunction "2_2") (pintype "input"))
      (node (ref "R43") (pin "1") (pinfunction "1_1") (pintype "input"))
    )
    (net (code "37") (name "Net-(D9-A)") (class "Default")
      (node (ref "C29") (pin "1") (pinfunction "1_1") (pintype "input"))
      (node (ref "D9") (pin "2") (pinfunction "A_2") (pintype "input"))
      (node (ref "R37") (pin "1") (pinfunction "1_1") (pintype "input"))
      (node (ref "U5") (pin "4") (pinfunction "VS_4") (pintype "input"))
    )
    (net (code "38") (name "Net-(D10-A)") (class "Default")
      (node (ref "C34") (pin "1") (pinfunction "1_1") (pintype "input"))
      (node (ref "D10") (pin "2") (pinfunction "A_2") (pintype "input"))
      (node (ref "R46") (pin "1") (pinfunction "1_1") (pintype "input"))
      (node (ref "U6") (pin "4") (pinfunction "VS_4") (pintype "input"))
    )
    (net (code "39") (name "Net-(D10-K)") (class "Default")
      (node (ref "C34") (pin "2") (pinfunction "2_2") (pintype "input"))
      (node (ref "D10") (pin "1") (pinfunction "K_1") (pintype "input"))
      (node (ref "D8") (pin "1") (pinfunction "K_1") (pintype "input"))
      (node (ref "U6") (pin "2") (pinfunction "VB_2") (pintype "input"))
    )
    (net (code "40") (name "Net-(D11-K)") (class "Default")
      (node (ref "D11") (pin "2") (pinfunction "K_2") (pintype "input"))
      (node (ref "Q5") (pin "1") (pinfunction "G_1") (pintype "input"))
      (node (ref "R38") (pin "2") (pinfunction "2_2") (pintype "input"))
      (node (ref "R39") (pin "1") (pinfunction "1_1") (pintype "input"))
    )
    (net (code "41") (name "Net-(D12-K)") (class "Default")
      (node (ref "D12") (pin "2") (pinfunction "K_2") (pintype "input"))
      (node (ref "Q7") (pin "1") (pinfunction "G_1") (pintype "input"))
      (node (ref "R47") (pin "2") (pinfunction "2_2") (pintype "input"))
      (node (ref "R48") (pin "1") (pinfunction "1_1") (pintype "input"))
    )
    (net (code "42") (name "Net-(D13-A)") (class "Default")
      (node (ref "D13") (pin "7") (pinfunction "A_7") (pintype "input"))
      (node (ref "R19") (pin "2") (pinfunction "2_2") (pintype "input"))
    )
    (net (code "43") (name "Net-(D13-B)") (class "Default")
      (node (ref "D13") (pin "8") (pinfunction "B_8") (pintype "input"))
      (node (ref "R20") (pin "2") (pinfunction "2_2") (pintype "input"))
    )
    (net (code "44") (name "Net-(D13-C)") (class "Default")
      (node (ref "D13") (pin "3") (pinfunction "C_3") (pintype "input"))
      (node (ref "R21") (pin "2") (pinfunction "2_2") (pintype "input"))
    )
    (net (code "45") (name "Net-(D13-D)") (class "Default")
      (node (ref "D13") (pin "2") (pinfunction "D_2") (pintype "input"))
      (node (ref "R22") (pin "2") (pinfunction "2_2") (pintype "input"))
    )
    (net (code "46") (name "Net-(D13-DIG1)") (class "Default")
      (node (ref "D13") (pin "9") (pinfunction "DIG1_9") (pintype "input"))
      (node (ref "Q2") (pin "3") (pinfunction "C_3") (pintype "input"))
    )
    (net (code "47") (name "Net-(D13-DIG2)") (class "Default")
      (node (ref "D13") (pin "6") (pinfunction "DIG2_6") (pintype "input"))
      (node (ref "Q3") (pin "3") (pinfunction "C_3") (pintype "input"))
    )
    (net (code "48") (name "Net-(D13-DP)") (class "Default")
      (node (ref "D13") (pin "5") (pinfunction "DP_5") (pintype "input"))
      (node (ref "R26") (pin "2") (pinfunction "2_2") (pintype "input"))
    )
    (net (code "49") (name "Net-(D13-E)") (class "Default")
      (node (ref "D13") (pin "1") (pinfunction "E_1") (pintype "input"))
      (node (ref "R23") (pin "2") (pinfunction "2_2") (pintype "input"))
    )
    (net (code "50") (name "Net-(D13-F)") (class "Default")
      (node (ref "D13") (pin "10") (pinfunction "F_10") (pintype "input"))
      (node (ref "R24") (pin "2") (pinfunction "2_2") (pintype "input"))
    )
    (net (code "51") (name "Net-(D13-G)") (class "Default")
      (node (ref "D13") (pin "4") (pinfunction "G_4") (pintype "input"))
      (node (ref "R25") (pin "2") (pinfunction "2_2") (pintype "input"))
    )
    (net (code "52") (name "Net-(P2-Pad1)") (class "Default")
      (node (ref "P2") (pin "1") (pinfunction "1_1") (pintype "input"))
      (node (ref "R40") (pin "2") (pinfunction "2_2") (pintype "input"))
      (node (ref "R41") (pin "2") (pinfunction "2_2") (pintype "input"))
    )
    (net (code "53") (name "Net-(PWR1-A)") (class "Default")
      (node (ref "PWR1") (pin "2") (pinfunction "A_2") (pintype "input"))
      (node (ref "R5") (pin "1") (pinfunction "1_1") (pintype "input"))
    )
    (net (code "54") (name "Net-(Q1-D)") (class "Default")
      (node (ref "P3") (pin "2") (pinfunction "2_2") (pintype "input"))
      (node (ref "Q1") (pin "3") (pinfunction "D_3") (pintype "input"))
    )
    (net (code "55") (name "Net-(Q1-G)") (class "Default")
      (node (ref "Q1") (pin "1") (pinfunction "G_1") (pintype "input"))
      (node (ref "R12") (pin "2") (pinfunction "2_2") (pintype "input"))
      (node (ref "R13") (pin "1") (pinfunction "1_1") (pintype "input"))
    )
    (net (code "56") (name "Net-(Q2-B)") (class "Default")
      (node (ref "Q2") (pin "1") (pinfunction "B_1") (pintype "input"))
      (node (ref "R14") (pin "1") (pinfunction "1_1") (pintype "input"))
    )
    (net (code "57") (name "Net-(Q3-B)") (class "Default")
      (node (ref "Q3") (pin "1") (pinfunction "B_1") (pintype "input"))
      (node (ref "R15") (pin "1") (pinfunction "1_1") (pintype "input"))
    )
    (net (code "58") (name "Net-(R6-Pad1)") (class "Default")
      (node (ref "R6") (pin "1") (pinfunction "1_1") (pintype "input"))
      (node (ref "R7") (pin "2") (pinfunction "2_2") (pintype "input"))
    )
    (net (code "59") (name "Net-(R10-Pad2)") (class "Default")
      (node (ref "R10") (pin "2") (pinfunction "2_2") (pintype "input"))
      (node (ref "R9") (pin "2") (pinfunction "2_2") (pintype "input"))
    )
    (net (code "60") (name "Net-(STA1-A)") (class "Default")
      (node (ref "R11") (pin "2") (pinfunction "2_2") (pintype "input"))
      (node (ref "STA1") (pin "2") (pinfunction "A_2") (pintype "input"))
    )
    (net (code "61") (name "Net-(U1-BOOT)") (class "Default")
      (node (ref "C1") (pin "1") (pinfunction "1_1") (pintype "input"))
      (node (ref "U1") (pin "1") (pinfunction "BOOT_1") (pintype "input"))
    )
    (net (code "62") (name "Net-(U1-COMP)") (class "Default")
      (node (ref "R4") (pin "2") (pinfunction "2_2") (pintype "input"))
      (node (ref "U1") (pin "6") (pinfunction "COMP_6") (pintype "input"))
    )
    (net (code "63") (name "Net-(U1-FB)") (class "Default")
      (node (ref "R1") (pin "1") (pinfunction "1_1") (pintype "input"))
      (node (ref "R2") (pin "2") (pinfunction "2_2") (pintype "input"))
      (node (ref "U1") (pin "5") (pinfunction "FB_5") (pintype "input"))
    )
    (net (code "64") (name "Net-(U1-RT{slash}CLK)") (class "Default")
      (node (ref "R3") (pin "2") (pinfunction "2_2") (pintype "input"))
      (node (ref "U1") (pin "4") (pinfunction "RT/CLK_4") (pintype "input"))
    )
    (net (code "65") (name "Net-(U1-SW)") (class "Default")
      (node (ref "C1") (pin "2") (pinfunction "2_2") (pintype "input"))
      (node (ref "L1") (pin "1") (pinfunction "1_1") (pintype "input"))
      (node (ref "U1") (pin "8") (pinfunction "SW_8") (pintype "input"))
    )
    (net (code "66") (name "Net-(U2-BS)") (class "Default")
      (node (ref "C14") (pin "1") (pinfunction "1_1") (pintype "input"))
      (node (ref "U2") (pin "1") (pinfunction "BS_1") (pintype "input"))
    )
    (net (code "67") (name "Net-(U2-FB)") (class "Default")
      (node (ref "C13") (pin "1") (pinfunction "1_1") (pintype "input"))
      (node (ref "R7") (pin "1") (pinfunction "1_1") (pintype "input"))
      (node (ref "R8") (pin "2") (pinfunction "2_2") (pintype "input"))
      (node (ref "U2") (pin "3") (pinfunction "FB_3") (pintype "input"))
    )
    (net (code "68") (name "Net-(U2-SW)") (class "Default")
      (node (ref "C14") (pin "2") (pinfunction "2_2") (pintype "input"))
      (node (ref "L2") (pin "2") (pinfunction "2_2") (pintype "input"))
      (node (ref "U2") (pin "6") (pinfunction "SW_6") (pintype "input"))
    )
    (net (code "69") (name "Net-(U3-OSC_IN{slash}PD0)") (class "Default")
      (node (ref "C17") (pin "1") (pinfunction "1_1") (pintype "input"))
      (node (ref "U3") (pin "5") (pinfunction "OSC_IN/PD0_5") (pintype "input"))
      (node (ref "Y1") (pin "1") (pinfunction "OSC1_1") (pintype "input"))
    )
    (net (code "70") (name "Net-(U3-OSC_OUT{slash}PD1)") (class "Default")
      (node (ref "C18") (pin "2") (pinfunction "2_2") (pintype "input"))
      (node (ref "U3") (pin "6") (pinfunction "OSC_OUT/PD1_6") (pintype "input"))
      (node (ref "Y1") (pin "3") (pinfunction "OSC2_3") (pintype "input"))
    )
    (net (code "71") (name "Net-(U3-VDDA)") (class "Default")
      (node (ref "C44") (pin "1") (pinfunction "1_1") (pintype "input"))
      (node (ref "FB2") (pin "2") (pinfunction "2_2") (pintype "input"))
      (node (ref "U3") (pin "9") (pinfunction "VDDA_9") (pintype "input"))
    )
    (net (code "72") (name "Net-(U3-VSSA)") (class "Default")
      (node (ref "C44") (pin "2") (pinfunction "2_2") (pintype "input"))
      (node (ref "FB3") (pin "1") (pinfunction "1_1") (pintype "input"))
      (node (ref "U3") (pin "8") (pinfunction "VSSA_8") (pintype "input"))
    )
    (net (code "73") (name "Net-(U4-OUT)") (class "Default")
      (node (ref "R31") (pin "2") (pinfunction "2_2") (pintype "input"))
      (node (ref "U4") (pin "6") (pinfunction "OUT_6") (pintype "input"))
    )
    (net (code "74") (name "Net-(U4-REF)") (class "Default")
      (node (ref "R27") (pin "1") (pinfunction "1_1") (pintype "input"))
      (node (ref "R28") (pin "2") (pinfunction "2_2") (pintype "input"))
      (node (ref "U4") (pin "1") (pinfunction "REF_1") (pintype "input"))
    )
    (net (code "75") (name "Net-(U5-DT)") (class "Default")
      (node (ref "R49") (pin "1") (pinfunction "1_1") (pintype "input"))
      (node (ref "U5") (pin "6") (pinfunction "DT_6") (pintype "input"))
    )
    (net (code "76") (name "Net-(U5-HO)") (class "Default")
      (node (ref "R33") (pin "1") (pinfunction "1_1") (pintype "input"))
      (node (ref "U5") (pin "3") (pinfunction "HO_3") (pintype "input"))
    )
    (net (code "77") (name "Net-(U5-LO)") (class "Default")
      (node (ref "R38") (pin "1") (pinfunction "1_1") (pintype "input"))
      (node (ref "U5") (pin "10") (pinfunction "LO_10") (pintype "input"))
    )
    (net (code "78") (name "Net-(U6-DT)") (class "Default")
      (node (ref "R50") (pin "1") (pinfunction "1_1") (pintype "input"))
      (node (ref "U6") (pin "6") (pinfunction "DT_6") (pintype "input"))
    )
    (net (code "79") (name "Net-(U6-HO)") (class "Default")
      (node (ref "R42") (pin "1") (pinfunction "1_1") (pintype "input"))
      (node (ref "U6") (pin "3") (pinfunction "HO_3") (pintype "input"))
    )
    (net (code "80") (name "Net-(U6-LO)") (class "Default")
      (node (ref "R47") (pin "1") (pinfunction "1_1") (pintype "input"))
      (node (ref "U6") (pin "10") (pinfunction "LO_10") (pintype "input"))
    )
    (net (code "81") (name "VBAT") (class "Default")
      (node (ref "C10") (pin "1") (pinfunction "1_1") (pintype "input"))
      (node (ref "C9") (pin "2") (pinfunction "2_2") (pintype "input"))
      (node (ref "D1") (pin "1") (pinfunction "A_1") (pintype "input"))
      (node (ref "P1") (pin "2") (pinfunction "2_2") (pintype "input"))
      (node (ref "R32") (pin "1") (pinfunction "1_1") (pintype "input"))
      (node (ref "U4") (pin "4") (pinfunction "IN+_4") (pintype "input"))
    )
    (net (code "82") (name "VBATO") (class "Default")
      (node (ref "C26") (pin "1") (pinfunction "1_1") (pintype "input"))
      (node (ref "C27") (pin "1") (pinfunction "1_1") (pintype "input"))
      (node (ref "C41") (pin "2") (pinfunction "2_2") (pintype "input"))
      (node (ref "C42") (pin "2") (pinfunction "2_2") (pintype "input"))
      (node (ref "D5") (pin "2") (pinfunction "A_2") (pintype "input"))
      (node (ref "Q4") (pin "2") (pinfunction "D_2") (pintype "input"))
      (node (ref "Q6") (pin "2") (pinfunction "D_2") (pintype "input"))
      (node (ref "R32") (pin "2") (pinfunction "2_2") (pintype "input"))
      (node (ref "U4") (pin "5") (pinfunction "IN-_5") (pintype "input"))
    )
    (net (code "83") (name "VCC3V3") (class "Default")
      (node (ref "C11") (pin "2") (pinfunction "2_2") (pintype "input"))
      (node (ref "C12") (pin "2") (pinfunction "2_2") (pintype "input"))
      (node (ref "C13") (pin "2") (pinfunction "2_2") (pintype "input"))
      (node (ref "C20") (pin "2") (pinfunction "2_2") (pintype "input"))
      (node (ref "C21") (pin "2") (pinfunction "2_2") (pintype "input"))
      (node (ref "C22") (pin "2") (pinfunction "2_2") (pintype "input"))
      (node (ref "C23") (pin "1") (pinfunction "1_1") (pintype "input"))
      (node (ref "FB2") (pin "1") (pinfunction "1_1") (pintype "input"))
      (node (ref "L2") (pin "1") (pinfunction "1_1") (pintype "input"))
      (node (ref "P4") (pin "1") (pinfunction "3V3_1") (pintype "input"))
      (node (ref "P5") (pin "3") (pinfunction "3_3") (pintype "input"))
      (node (ref "Q2") (pin "2") (pinfunction "E_2") (pintype "input"))
      (node (ref "Q3") (pin "2") (pinfunction "E_2") (pintype "input"))
      (node (ref "R11") (pin "1") (pinfunction "1_1") (pintype "input"))
      (node (ref "R18") (pin "1") (pinfunction "1_1") (pintype "input"))
      (node (ref "R28") (pin "1") (pinfunction "1_1") (pintype "input"))
      (node (ref "R5") (pin "2") (pinfunction "2_2") (pintype "input"))
      (node (ref "R6") (pin "2") (pinfunction "2_2") (pintype "input"))
      (node (ref "R9") (pin "1") (pinfunction "1_1") (pintype "input"))
      (node (ref "U3") (pin "1") (pinfunction "VBAT_1") (pintype "input"))
      (node (ref "U3") (pin "24") (pinfunction "VDD_VIO_1_24") (pintype "input"))
      (node (ref "U3") (pin "36") (pinfunction "VDD_2_36") (pintype "input"))
      (node (ref "U3") (pin "48") (pinfunction "VDD_VIO_3_48") (pintype "input"))
      (node (ref "U4") (pin "3") (pinfunction "V+_3") (pintype "input"))
    )
    (net (code "84") (name "VCC12V") (class "Default")
      (node (ref "C15") (pin "2") (pinfunction "2_2") (pintype "input"))
      (node (ref "C16") (pin "2") (pinfunction "2_2") (pintype "input"))
      (node (ref "C2") (pin "2") (pinfunction "2_2") (pintype "input"))
      (node (ref "C3") (pin "1") (pinfunction "1_1") (pintype "input"))
      (node (ref "C33") (pin "2") (pinfunction "2_2") (pintype "input"))
      (node (ref "C4") (pin "2") (pinfunction "2_2") (pintype "input"))
      (node (ref "C40") (pin "2") (pinfunction "2_2") (pintype "input"))
      (node (ref "D4") (pin "2") (pinfunction "A_2") (pintype "input"))
      (node (ref "D8") (pin "2") (pinfunction "A_2") (pintype "input"))
      (node (ref "L1") (pin "2") (pinfunction "2_2") (pintype "input"))
      (node (ref "P3") (pin "1") (pinfunction "1_1") (pintype "input"))
      (node (ref "P5") (pin "2") (pinfunction "2_2") (pintype "input"))
      (node (ref "R1") (pin "2") (pinfunction "2_2") (pintype "input"))
      (node (ref "U2") (pin "4") (pinfunction "EN_4") (pintype "input"))
      (node (ref "U2") (pin "5") (pinfunction "IN_5") (pintype "input"))
      (node (ref "U5") (pin "1") (pinfunction "VCC_1") (pintype "input"))
      (node (ref "U6") (pin "1") (pinfunction "VCC_1") (pintype "input"))
    )
    (net (code "85") (name "unconnected-(ON/OFF1-Pad1)") (class "Default")
      (node (ref "ON/OFF1") (pin "1") (pinfunction "1_1") (pintype "input"))
    )
    (net (code "86") (name "unconnected-(ON/OFF1-Pad2)") (class "Default")
      (node (ref "ON/OFF1") (pin "2") (pinfunction "2_2") (pintype "input"))
    )
    (net (code "87") (name "unconnected-(P4-NC-Pad6)") (class "Default")
      (node (ref "P4") (pin "6") (pinfunction "NC_6") (pintype "input+no_connect"))
    )
    (net (code "88") (name "unconnected-(P4-NC-Pad8)") (class "Default")
      (node (ref "P4") (pin "8") (pinfunction "NC_8") (pintype "input+no_connect"))
    )
    (net (code "89") (name "unconnected-(U3-PA11{slash}USB1DM-Pad32)") (class "Default")
      (node (ref "U3") (pin "32") (pinfunction "PA11/USB1DM_32") (pintype "input"))
    )
    (net (code "90") (name "unconnected-(U3-PA12{slash}USB1DP-Pad33)") (class "Default")
      (node (ref "U3") (pin "33") (pinfunction "PA12/USB1DP_33") (pintype "input"))
    )
    (net (code "91") (name "unconnected-(U3-PB9-Pad46)") (class "Default")
      (node (ref "U3") (pin "46") (pinfunction "PB9_46") (pintype "input+no_connect"))
    )
    (net (code "92") (name "unconnected-(U3-PB10-Pad21)") (class "Default")
      (node (ref "U3") (pin "21") (pinfunction "PB10_21") (pintype "input+no_connect"))
    )
    (net (code "93") (name "unconnected-(U3-PB11-Pad22)") (class "Default")
      (node (ref "U3") (pin "22") (pinfunction "PB11_22") (pintype "input+no_connect"))
    )
    (net (code "94") (name "unconnected-(U3-PB12-Pad25)") (class "Default")
      (node (ref "U3") (pin "25") (pinfunction "PB12_25") (pintype "input+no_connect"))
    )
    (net (code "95") (name "unconnected-(U3-PB13-Pad26)") (class "Default")
      (node (ref "U3") (pin "26") (pinfunction "PB13_26") (pintype "input+no_connect"))
    )
    (net (code "96") (name "unconnected-(U3-PB14-Pad27)") (class "Default")
      (node (ref "U3") (pin "27") (pinfunction "PB14_27") (pintype "input+no_connect"))
    )
    (net (code "97") (name "unconnected-(U3-PB15-Pad28)") (class "Default")
      (node (ref "U3") (pin "28") (pinfunction "PB15_28") (pintype "input+no_connect"))
    )
    (net (code "98") (name "unconnected-(U3-PC13{slash}TAMPER_RTC-Pad2)") (class "Default")
      (node (ref "U3") (pin "2") (pinfunction "PC13/TAMPER_RTC_2") (pintype "input+no_connect"))
    )
    (net (code "99") (name "unconnected-(U3-PC14{slash}OSC32IN-Pad3)") (class "Default")
      (node (ref "U3") (pin "3") (pinfunction "PC14/OSC32IN_3") (pintype "input+no_connect"))
    )
    (net (code "100") (name "unconnected-(U3-PC15{slash}OSC32OUT-Pad4)") (class "Default")
      (node (ref "U3") (pin "4") (pinfunction "PC15/OSC32OUT_4") (pintype "input+no_connect"))
    )
    (net (code "101") (name "unconnected-(U5-NC-Pad5)") (class "Default")
      (node (ref "U5") (pin "5") (pinfunction "NC_5") (pintype "input"))
    )
    (net (code "102") (name "unconnected-(U6-NC-Pad5)") (class "Default")
      (node (ref "U6") (pin "5") (pinfunction "NC_5") (pintype "input"))
    )
    (net (code "103") (name "unconnected-(U7-Pad0)") (class "Default")
      (node (ref "U7") (pin "0") (pinfunction "0_0") (pintype "input"))
    )
  )
)
